# FAN.net
KiCad netlist of a schematic drawn in Altium Designer
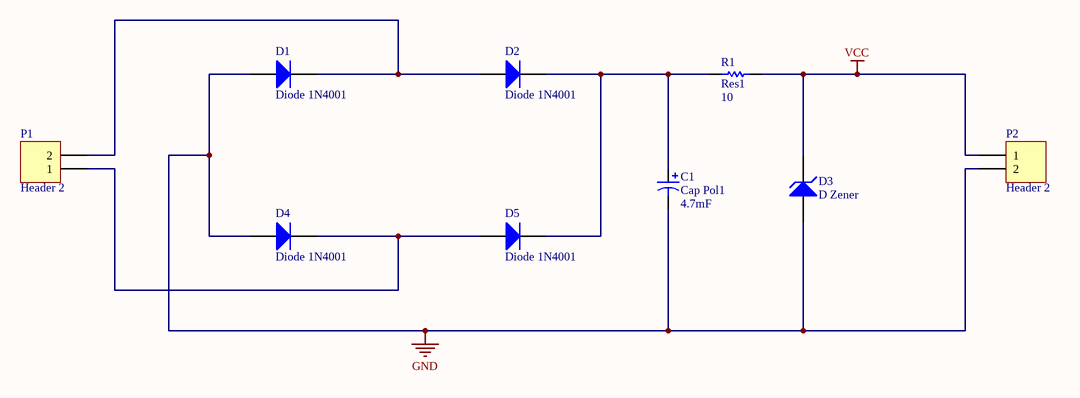
[diagram p0: FAN.SchDoc]

(export (version "E")
  (design (tool "Eeschema 10.0.6"))
  (components
    (comp (ref "C1")
      (value "Cap Pol1")
      (footprint "RB7.6-15")
      (description "Polarized Capacitor (Radial)")
      (fields (field (name "ALTIUM_VALUE") "4.7mF") (field (name "PUBLISHER") "Altium Limited"))
      (libsource (lib "Miscellaneous Devices") (part "Cap Pol1"))
    )
    (comp (ref "D1")
      (value "Diode 1N4001")
      (footprint "DO-41")
      (description "1 Amp General Purpose Rectifier")
      (fields (field (name "PUBLISHER") "Altium Limited"))
      (libsource (lib "Miscellaneous Devices") (part "Diode 1N4001"))
    )
    (comp (ref "D2")
      (value "Diode 1N4001")
      (footprint "DO-41")
      (description "1 Amp General Purpose Rectifier")
      (fields (field (name "PUBLISHER") "Altium Limited"))
      (libsource (lib "Miscellaneous Devices") (part "Diode 1N4001"))
    )
    (comp (ref "D3")
      (value "D Zener")
      (footprint "DIODE-0.7")
      (description "Zener Diode")
      (fields (field (name "PUBLISHER") "Altium Limited"))
      (libsource (lib "Miscellaneous Devices") (part "D Zener"))
    )
    (comp (ref "D4")
      (value "Diode 1N4001")
      (footprint "DO-41")
      (description "1 Amp General Purpose Rectifier")
      (fields (field (name "PUBLISHER") "Altium Limited"))
      (libsource (lib "Miscellaneous Devices") (part "Diode 1N4001"))
    )
    (comp (ref "D5")
      (value "Diode 1N4001")
      (footprint "DO-41")
      (description "1 Amp General Purpose Rectifier")
      (fields (field (name "PUBLISHER") "Altium Limited"))
      (libsource (lib "Miscellaneous Devices") (part "Diode 1N4001"))
    )
    (comp (ref "P1")
      (value "Header 2")
      (footprint "HDR1X2")
      (description "Header, 2-Pin")
      (fields (field (name "PUBLISHER") "Altium Limited"))
      (libsource (lib "") (part "Header 2_1"))
    )
    (comp (ref "P2")
      (value "Header 2")
      (footprint "HDR1X2")
      (description "Header, 2-Pin")
      (fields (field (name "PUBLISHER") "Altium Limited"))
      (libsource (lib "Miscellaneous Connectors") (part "Header 2"))
    )
    (comp (ref "R1")
      (value "Res1")
      (footprint "AXIAL-0.3")
      (description "Resistor")
      (fields (field (name "ALTIUM_VALUE") "10") (field (name "PUBLISHER") "Altium Limited"))
      (libsource (lib "Miscellaneous Devices") (part "Res1"))
    )
  )
  (nets
    (net (code "1") (name "GND") (class "Default")
      (node (ref "C1") (pin "2") (pinfunction "2_2") (pintype "passive"))
      (node (ref "D1") (pin "1") (pinfunction "A_1") (pintype "passive"))
      (node (ref "D3") (pin "1") (pinfunction "A_1") (pintype "passive"))
      (node (ref "D4") (pin "1") (pinfunction "A_1") (pintype "passive"))
      (node (ref "P2") (pin "2") (pinfunction "2_2") (pintype "passive"))
    )
    (net (code "2") (name "Net-(D1-K)") (class "Default")
      (node (ref "D1") (pin "2") (pinfunction "K_2") (pintype "passive"))
      (node (ref "D2") (pin "1") (pinfunction "A_1") (pintype "passive"))
      (node (ref "P1") (pin "2") (pinfunction "2_2") (pintype "passive"))
    )
    (net (code "3") (name "Net-(D2-K)") (class "Default")
      (node (ref "C1") (pin "1") (pinfunction "1_1") (pintype "passive"))
      (node (ref "D2") (pin "2") (pinfunction "K_2") (pintype "passive"))
      (node (ref "D5") (pin "2") (pinfunction "K_2") (pintype "passive"))
      (node (ref "R1") (pin "1") (pinfunction "1_1") (pintype "passive"))
    )
    (net (code "4") (name "Net-(D4-K)") (class "Default")
      (node (ref "D4") (pin "2") (pinfunction "K_2") (pintype "passive"))
      (node (ref "D5") (pin "1") (pinfunction "A_1") (pintype "passive"))
      (node (ref "P1") (pin "1") (pinfunction "1_1") (pintype "passive"))
    )
    (net (code "5") (name "VCC") (class "Default")
      (node (ref "D3") (pin "2") (pinfunction "K_2") (pintype "passive"))
      (node (ref "P2") (pin "1") (pinfunction "1_1") (pintype "passive"))
      (node (ref "R1") (pin "2") (pinfunction "2_2") (pintype "passive"))
    )
  )
)
